# ProPrj_ZC95_FrontPanelControls_v1_1.net
KiCad netlist of a schematic drawn in EasyEDA Pro
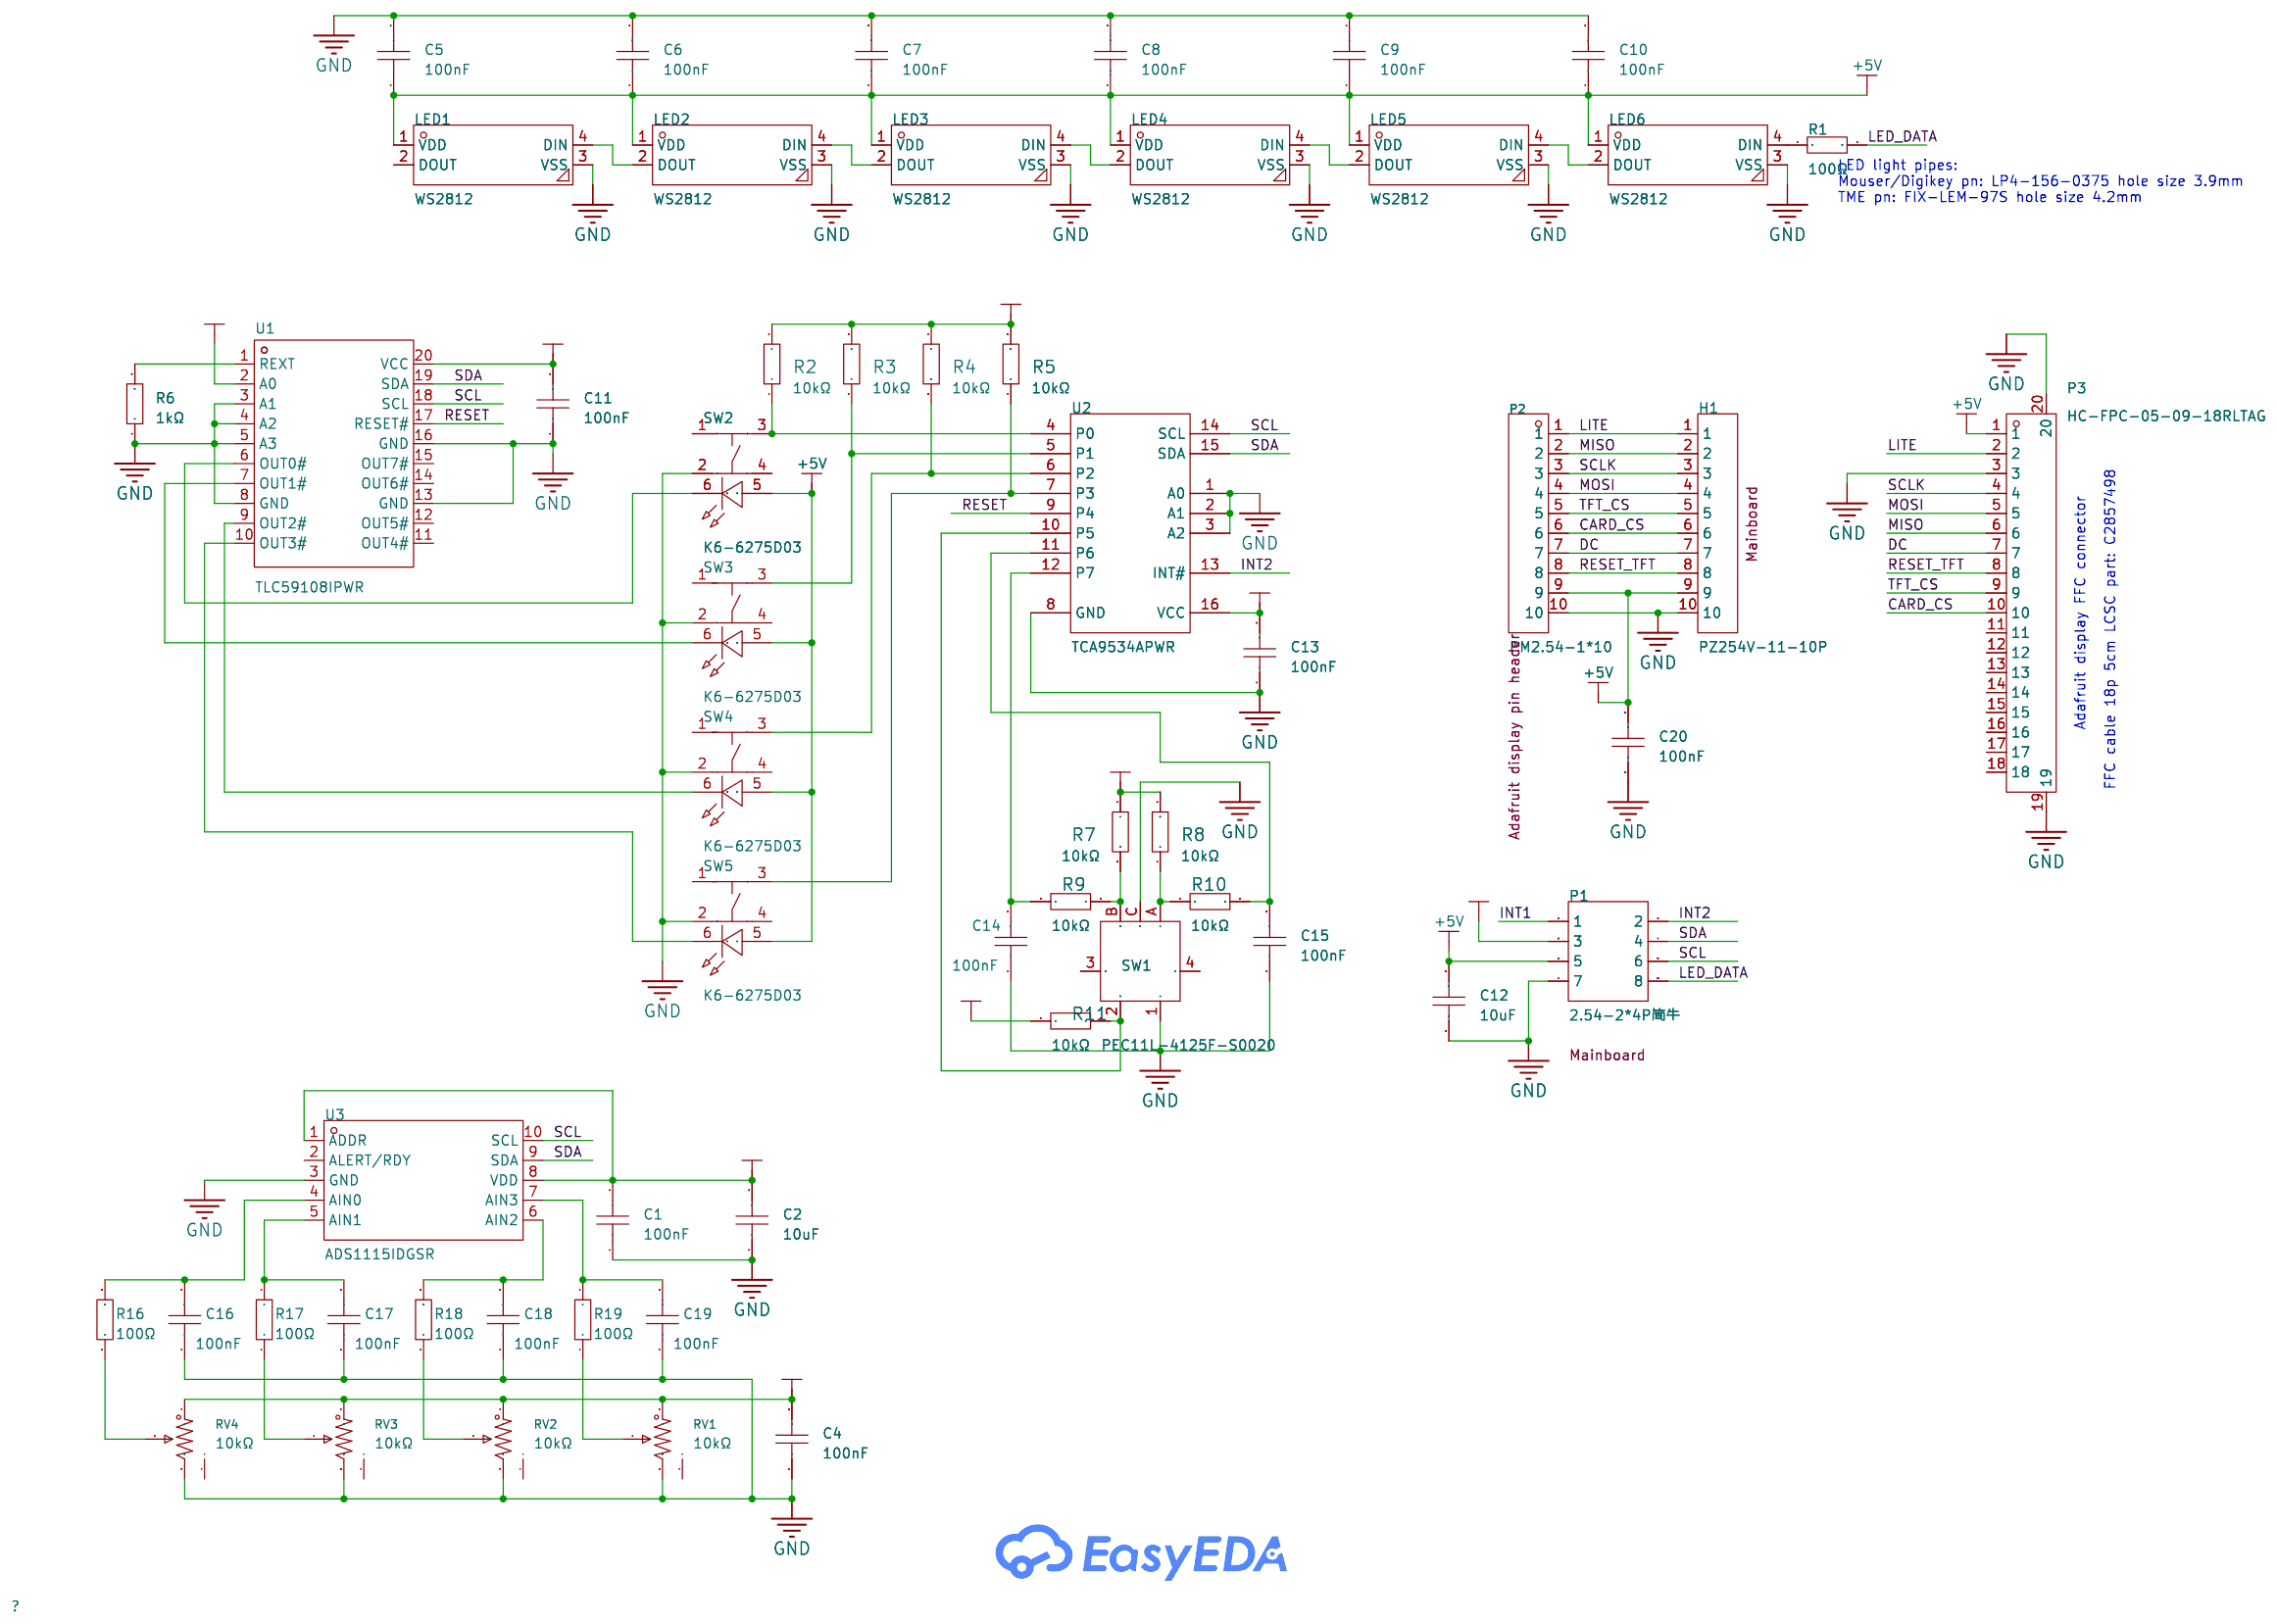
[diagram p0: schematic sheet]

(export (version "E")
  (design (tool "Eeschema 10.0.6"))
  (components
    (comp (ref "C1")
      (value "100nF")
      (footprint "easyedapro:C0603")
      (description "Capacitance:100nF Tolerance:±10% Tolerance:±10% Voltage Rating:50V Temperature Coefficient:X7R")
      (fields
        (field (name "Manufacturer Part") "CC0603KRX7R9BB104")
        (field (name "Manufacturer") "YAGEO(国巨)")
      )
      (libsource (lib "easyedapro") (part "CC0603KRX7R9BB104"))
    )
    (comp (ref "C2")
      (value "10uF")
      (footprint "easyedapro:C0603")
      (description "Capacitance:10uF Tolerance:±10% Tolerance:±10% Voltage Rating:10V Temperature Coefficient:X5R")
      (fields
        (field (name "Manufacturer Part") "CL10A106KP8NNNC")
        (field (name "Manufacturer") "SAMSUNG(三星)")
      )
      (libsource (lib "easyedapro") (part "CL10A106KP8NNNC"))
    )
    (comp (ref "C4")
      (value "100nF")
      (footprint "easyedapro:C0603")
      (description "Capacitance:100nF Tolerance:±10% Tolerance:±10% Voltage Rating:50V Temperature Coefficient:X7R")
      (fields
        (field (name "Manufacturer Part") "CC0603KRX7R9BB104")
        (field (name "Manufacturer") "YAGEO(国巨)")
      )
      (libsource (lib "easyedapro") (part "CC0603KRX7R9BB104"))
    )
    (comp (ref "C5")
      (value "100nF")
      (footprint "easyedapro:C0603")
      (description "Capacitance:100nF Tolerance:±10% Tolerance:±10% Voltage Rating:50V Temperature Coefficient:X7R")
      (fields
        (field (name "Manufacturer Part") "CC0603KRX7R9BB104")
        (field (name "Manufacturer") "YAGEO(国巨)")
      )
      (libsource (lib "easyedapro") (part "CC0603KRX7R9BB104"))
    )
    (comp (ref "C6")
      (value "100nF")
      (footprint "easyedapro:C0603")
      (description "Capacitance:100nF Tolerance:±10% Tolerance:±10% Voltage Rating:50V Temperature Coefficient:X7R")
      (fields
        (field (name "Manufacturer Part") "CC0603KRX7R9BB104")
        (field (name "Manufacturer") "YAGEO(国巨)")
      )
      (libsource (lib "easyedapro") (part "CC0603KRX7R9BB104"))
    )
    (comp (ref "C7")
      (value "100nF")
      (footprint "easyedapro:C0603")
      (description "Capacitance:100nF Tolerance:±10% Tolerance:±10% Voltage Rating:50V Temperature Coefficient:X7R")
      (fields
        (field (name "Manufacturer Part") "CC0603KRX7R9BB104")
        (field (name "Manufacturer") "YAGEO(国巨)")
      )
      (libsource (lib "easyedapro") (part "CC0603KRX7R9BB104"))
    )
    (comp (ref "C8")
      (value "100nF")
      (footprint "easyedapro:C0603")
      (description "Capacitance:100nF Tolerance:±10% Tolerance:±10% Voltage Rating:50V Temperature Coefficient:X7R")
      (fields
        (field (name "Manufacturer Part") "CC0603KRX7R9BB104")
        (field (name "Manufacturer") "YAGEO(国巨)")
      )
      (libsource (lib "easyedapro") (part "CC0603KRX7R9BB104"))
    )
    (comp (ref "C9")
      (value "100nF")
      (footprint "easyedapro:C0603")
      (description "Capacitance:100nF Tolerance:±10% Tolerance:±10% Voltage Rating:50V Temperature Coefficient:X7R")
      (fields
        (field (name "Manufacturer Part") "CC0603KRX7R9BB104")
        (field (name "Manufacturer") "YAGEO(国巨)")
      )
      (libsource (lib "easyedapro") (part "CC0603KRX7R9BB104"))
    )
    (comp (ref "C10")
      (value "100nF")
      (footprint "easyedapro:C0603")
      (description "Capacitance:100nF Tolerance:±10% Tolerance:±10% Voltage Rating:50V Temperature Coefficient:X7R")
      (fields
        (field (name "Manufacturer Part") "CC0603KRX7R9BB104")
        (field (name "Manufacturer") "YAGEO(国巨)")
      )
      (libsource (lib "easyedapro") (part "CC0603KRX7R9BB104"))
    )
    (comp (ref "C11")
      (value "100nF")
      (footprint "easyedapro:C0603")
      (description "Capacitance:100nF Tolerance:±10% Tolerance:±10% Voltage Rating:50V Temperature Coefficient:X7R")
      (fields
        (field (name "Manufacturer Part") "CC0603KRX7R9BB104")
        (field (name "Manufacturer") "YAGEO(国巨)")
      )
      (libsource (lib "easyedapro") (part "CC0603KRX7R9BB104"))
    )
    (comp (ref "C12")
      (value "10uF")
      (footprint "easyedapro:C0603")
      (description "Capacitance:10uF Tolerance:±10% Tolerance:±10% Voltage Rating:10V Temperature Coefficient:X5R")
      (fields
        (field (name "Manufacturer Part") "CL10A106KP8NNNC")
        (field (name "Manufacturer") "SAMSUNG(三星)")
      )
      (libsource (lib "easyedapro") (part "CL10A106KP8NNNC"))
    )
    (comp (ref "C13")
      (value "100nF")
      (footprint "easyedapro:C0603")
      (description "Capacitance:100nF Tolerance:±10% Tolerance:±10% Voltage Rating:50V Temperature Coefficient:X7R")
      (fields
        (field (name "Manufacturer Part") "CC0603KRX7R9BB104")
        (field (name "Manufacturer") "YAGEO(国巨)")
      )
      (libsource (lib "easyedapro") (part "CC0603KRX7R9BB104"))
    )
    (comp (ref "C14")
      (value "100nF")
      (footprint "easyedapro:C0603")
      (description "Capacitance:100nF Tolerance:±10% Tolerance:±10% Voltage Rating:50V Temperature Coefficient:X7R")
      (fields
        (field (name "Manufacturer Part") "CC0603KRX7R9BB104")
        (field (name "Manufacturer") "YAGEO(国巨)")
      )
      (libsource (lib "easyedapro") (part "CC0603KRX7R9BB104"))
    )
    (comp (ref "C15")
      (value "100nF")
      (footprint "easyedapro:C0603")
      (description "Capacitance:100nF Tolerance:±10% Tolerance:±10% Voltage Rating:50V Temperature Coefficient:X7R")
      (fields
        (field (name "Manufacturer Part") "CC0603KRX7R9BB104")
        (field (name "Manufacturer") "YAGEO(国巨)")
      )
      (libsource (lib "easyedapro") (part "CC0603KRX7R9BB104"))
    )
    (comp (ref "C16")
      (value "100nF")
      (footprint "easyedapro:C0603")
      (description "Capacitance:100nF Tolerance:±10% Tolerance:±10% Voltage Rating:50V Temperature Coefficient:X7R")
      (fields
        (field (name "Manufacturer Part") "CC0603KRX7R9BB104")
        (field (name "Manufacturer") "YAGEO(国巨)")
      )
      (libsource (lib "easyedapro") (part "CC0603KRX7R9BB104"))
    )
    (comp (ref "C17")
      (value "100nF")
      (footprint "easyedapro:C0603")
      (description "Capacitance:100nF Tolerance:±10% Tolerance:±10% Voltage Rating:50V Temperature Coefficient:X7R")
      (fields
        (field (name "Manufacturer Part") "CC0603KRX7R9BB104")
        (field (name "Manufacturer") "YAGEO(国巨)")
      )
      (libsource (lib "easyedapro") (part "CC0603KRX7R9BB104"))
    )
    (comp (ref "C18")
      (value "100nF")
      (footprint "easyedapro:C0603")
      (description "Capacitance:100nF Tolerance:±10% Tolerance:±10% Voltage Rating:50V Temperature Coefficient:X7R")
      (fields
        (field (name "Manufacturer Part") "CC0603KRX7R9BB104")
        (field (name "Manufacturer") "YAGEO(国巨)")
      )
      (libsource (lib "easyedapro") (part "CC0603KRX7R9BB104"))
    )
    (comp (ref "C19")
      (value "100nF")
      (footprint "easyedapro:C0603")
      (description "Capacitance:100nF Tolerance:±10% Tolerance:±10% Voltage Rating:50V Temperature Coefficient:X7R")
      (fields
        (field (name "Manufacturer Part") "CC0603KRX7R9BB104")
        (field (name "Manufacturer") "YAGEO(国巨)")
      )
      (libsource (lib "easyedapro") (part "CC0603KRX7R9BB104"))
    )
    (comp (ref "C20")
      (value "100nF")
      (footprint "easyedapro:C0603")
      (description "Capacitance:100nF Tolerance:±10% Tolerance:±10% Voltage Rating:50V Temperature Coefficient:X7R")
      (fields
        (field (name "Manufacturer Part") "CC0603KRX7R9BB104")
        (field (name "Manufacturer") "YAGEO(国巨)")
      )
      (libsource (lib "easyedapro") (part "CC0603KRX7R9BB104"))
    )
    (comp (ref "H1")
      (value "PZ254V-11-10P")
      (footprint "easyedapro:HDR-TH_10P-P2.54-V-M")
      (fields (field (name "Manufacturer") "XFCN(兴飞)") (field (name "Comment") "Mainboard"))
      (libsource (lib "easyedapro") (part "PZ254V-11-10P"))
    )
    (comp (ref "LED1")
      (value "WS2812")
      (footprint "easyedapro:LED-SMD_4P-L5.0-W5.0-TL_WS2812B-B")
      (fields (field (name "Manufacturer") "worldsemi"))
      (libsource (lib "easyedapro") (part "WS2812B-B/W"))
    )
    (comp (ref "LED2")
      (value "WS2812")
      (footprint "easyedapro:LED-SMD_4P-L5.0-W5.0-TL_WS2812B-B")
      (fields (field (name "Manufacturer") "worldsemi"))
      (libsource (lib "easyedapro") (part "WS2812B-B/W"))
    )
    (comp (ref "LED3")
      (value "WS2812")
      (footprint "easyedapro:LED-SMD_4P-L5.0-W5.0-TL_WS2812B-B")
      (fields (field (name "Manufacturer") "worldsemi"))
      (libsource (lib "easyedapro") (part "WS2812B-B/W"))
    )
    (comp (ref "LED4")
      (value "WS2812")
      (footprint "easyedapro:LED-SMD_4P-L5.0-W5.0-TL_WS2812B-B")
      (fields (field (name "Manufacturer") "worldsemi"))
      (libsource (lib "easyedapro") (part "WS2812B-B/W"))
    )
    (comp (ref "LED5")
      (value "WS2812")
      (footprint "easyedapro:LED-SMD_4P-L5.0-W5.0-TL_WS2812B-B")
      (fields (field (name "Manufacturer") "worldsemi"))
      (libsource (lib "easyedapro") (part "WS2812B-B/W"))
    )
    (comp (ref "LED6")
      (value "WS2812")
      (footprint "easyedapro:LED-SMD_4P-L5.0-W5.0-TL_WS2812B-B")
      (fields (field (name "Manufacturer") "worldsemi"))
      (libsource (lib "easyedapro") (part "WS2812B-B/W"))
    )
    (comp (ref "P1")
      (value "2.54-2*4P简牛")
      (footprint "easyedapro:IDC-TH_8P-P2.54-V-R2-C4-S2.54")
      (fields (field (name "Manufacturer") "BOOMELE(博穆精密)") (field (name "Comment") "Mainboard"))
      (libsource (lib "easyedapro") (part "HDR-IDC-2.54-2X4P"))
    )
    (comp (ref "P2")
      (value "PM2.54-1*10")
      (footprint "easyedapro:HDR-TH_10P-P2.54-V-F")
      (fields
        (field (name "Manufacturer") "ZHOURI(洲日)")
        (field (name "Comment") "Adafruit display pin header")
      )
      (libsource (lib "easyedapro") (part "PM2.54-1*10"))
    )
    (comp (ref "P3")
      (value "HC-FPC-05-09-18RLTAG")
      (footprint "easyedapro:FPC-SMD_18P-P0.50_HC-FPC-05-09-18RLTAG")
      (fields (field (name "Manufacturer") "HCTL(华灿天禄)"))
      (libsource (lib "easyedapro") (part "HC-FPC-05-09-18RLTAG"))
    )
    (comp (ref "R1")
      (value "100Ω")
      (footprint "easyedapro:R0603")
      (fields
        (field (name "Manufacturer Part") "0603WAF1000T5E")
        (field (name "Manufacturer") "UNI-ROYAL(厚声)")
      )
      (libsource (lib "easyedapro") (part "0603WAF1000T5E"))
    )
    (comp (ref "R2")
      (value "10kΩ")
      (footprint "easyedapro:R0603")
      (fields
        (field (name "Manufacturer Part") "0603WAF1002T5E")
        (field (name "Manufacturer") "UNI-ROYAL(厚声)")
      )
      (libsource (lib "easyedapro") (part "0603WAF1002T5E"))
    )
    (comp (ref "R3")
      (value "10kΩ")
      (footprint "easyedapro:R0603")
      (fields
        (field (name "Manufacturer Part") "0603WAF1002T5E")
        (field (name "Manufacturer") "UNI-ROYAL(厚声)")
      )
      (libsource (lib "easyedapro") (part "0603WAF1002T5E"))
    )
    (comp (ref "R4")
      (value "10kΩ")
      (footprint "easyedapro:R0603")
      (fields
        (field (name "Manufacturer Part") "0603WAF1002T5E")
        (field (name "Manufacturer") "UNI-ROYAL(厚声)")
      )
      (libsource (lib "easyedapro") (part "0603WAF1002T5E"))
    )
    (comp (ref "R5")
      (value "10kΩ")
      (footprint "easyedapro:R0603")
      (fields
        (field (name "Manufacturer Part") "0603WAF1002T5E")
        (field (name "Manufacturer") "UNI-ROYAL(厚声)")
      )
      (libsource (lib "easyedapro") (part "0603WAF1002T5E"))
    )
    (comp (ref "R6")
      (value "1kΩ")
      (footprint "easyedapro:R0603")
      (fields
        (field (name "Manufacturer Part") "0603WAF1001T5E")
        (field (name "Manufacturer") "UNI-ROYAL(厚声)")
      )
      (libsource (lib "easyedapro") (part "0603WAF1001T5E"))
    )
    (comp (ref "R7")
      (value "10kΩ")
      (footprint "easyedapro:R0603")
      (fields
        (field (name "Manufacturer Part") "0603WAF1002T5E")
        (field (name "Manufacturer") "UNI-ROYAL(厚声)")
      )
      (libsource (lib "easyedapro") (part "0603WAF1002T5E"))
    )
    (comp (ref "R8")
      (value "10kΩ")
      (footprint "easyedapro:R0603")
      (fields
        (field (name "Manufacturer Part") "0603WAF1002T5E")
        (field (name "Manufacturer") "UNI-ROYAL(厚声)")
      )
      (libsource (lib "easyedapro") (part "0603WAF1002T5E"))
    )
    (comp (ref "R9")
      (value "10kΩ")
      (footprint "easyedapro:R0603")
      (fields
        (field (name "Manufacturer Part") "0603WAF1002T5E")
        (field (name "Manufacturer") "UNI-ROYAL(厚声)")
      )
      (libsource (lib "easyedapro") (part "0603WAF1002T5E"))
    )
    (comp (ref "R10")
      (value "10kΩ")
      (footprint "easyedapro:R0603")
      (fields
        (field (name "Manufacturer Part") "0603WAF1002T5E")
        (field (name "Manufacturer") "UNI-ROYAL(厚声)")
      )
      (libsource (lib "easyedapro") (part "0603WAF1002T5E"))
    )
    (comp (ref "R11")
      (value "10kΩ")
      (footprint "easyedapro:R0603")
      (fields
        (field (name "Manufacturer Part") "0603WAF1002T5E")
        (field (name "Manufacturer") "UNI-ROYAL(厚声)")
      )
      (libsource (lib "easyedapro") (part "0603WAF1002T5E"))
    )
    (comp (ref "R16")
      (value "100Ω")
      (footprint "easyedapro:R0603")
      (fields
        (field (name "Manufacturer Part") "0603WAF1000T5E")
        (field (name "Manufacturer") "UNI-ROYAL(厚声)")
      )
      (libsource (lib "easyedapro") (part "0603WAF1000T5E"))
    )
    (comp (ref "R17")
      (value "100Ω")
      (footprint "easyedapro:R0603")
      (fields
        (field (name "Manufacturer Part") "0603WAF1000T5E")
        (field (name "Manufacturer") "UNI-ROYAL(厚声)")
      )
      (libsource (lib "easyedapro") (part "0603WAF1000T5E"))
    )
    (comp (ref "R18")
      (value "100Ω")
      (footprint "easyedapro:R0603")
      (fields
        (field (name "Manufacturer Part") "0603WAF1000T5E")
        (field (name "Manufacturer") "UNI-ROYAL(厚声)")
      )
      (libsource (lib "easyedapro") (part "0603WAF1000T5E"))
    )
    (comp (ref "R19")
      (value "100Ω")
      (footprint "easyedapro:R0603")
      (fields
        (field (name "Manufacturer Part") "0603WAF1000T5E")
        (field (name "Manufacturer") "UNI-ROYAL(厚声)")
      )
      (libsource (lib "easyedapro") (part "0603WAF1000T5E"))
    )
    (comp (ref "RV1")
      (value "10kΩ")
      (footprint "easyedapro:RES-ADJ-TH_RK09L1140A65")
      (fields
        (field (name "Manufacturer Part") "RK09L1140A2U")
        (field (name "Manufacturer") "ALPSALPINE(阿尔卑斯阿尔派)")
      )
      (libsource (lib "easyedapro") (part "RK09L1140A2U"))
    )
    (comp (ref "RV2")
      (value "10kΩ")
      (footprint "easyedapro:RES-ADJ-TH_RK09L1140A65")
      (fields
        (field (name "Manufacturer Part") "RK09L1140A2U")
        (field (name "Manufacturer") "ALPSALPINE(阿尔卑斯阿尔派)")
      )
      (libsource (lib "easyedapro") (part "RK09L1140A2U"))
    )
    (comp (ref "RV3")
      (value "10kΩ")
      (footprint "easyedapro:RES-ADJ-TH_RK09L1140A65")
      (fields
        (field (name "Manufacturer Part") "RK09L1140A2U")
        (field (name "Manufacturer") "ALPSALPINE(阿尔卑斯阿尔派)")
      )
      (libsource (lib "easyedapro") (part "RK09L1140A2U"))
    )
    (comp (ref "RV4")
      (value "10kΩ")
      (footprint "easyedapro:RES-ADJ-TH_RK09L1140A65")
      (fields
        (field (name "Manufacturer Part") "RK09L1140A2U")
        (field (name "Manufacturer") "ALPSALPINE(阿尔卑斯阿尔派)")
      )
      (libsource (lib "easyedapro") (part "RK09L1140A2U"))
    )
    (comp (ref "SW1")
      (value "PEC11L-4125F-S0020")
      (footprint "easyedapro:SW-TH_PEC11L-4125F-S0020")
      (fields (field (name "Manufacturer") "BOURNS"))
      (libsource (lib "easyedapro") (part "PEC11L-4125F-S0020"))
    )
    (comp (ref "SW2")
      (value "K6-6275D03")
      (footprint "easyedapro:SW-TH_K6-6275D03")
      (fields (field (name "Manufacturer") "韩国韩荣"))
      (libsource (lib "easyedapro") (part "K6-6275D03"))
    )
    (comp (ref "SW3")
      (value "K6-6275D03")
      (footprint "easyedapro:SW-TH_K6-6275D03")
      (fields (field (name "Manufacturer") "韩国韩荣"))
      (libsource (lib "easyedapro") (part "K6-6275D03"))
    )
    (comp (ref "SW4")
      (value "K6-6275D03")
      (footprint "easyedapro:SW-TH_K6-6275D03")
      (fields (field (name "Manufacturer") "韩国韩荣"))
      (libsource (lib "easyedapro") (part "K6-6275D03"))
    )
    (comp (ref "SW5")
      (value "K6-6275D03")
      (footprint "easyedapro:SW-TH_K6-6275D03")
      (fields (field (name "Manufacturer") "韩国韩荣"))
      (libsource (lib "easyedapro") (part "K6-6275D03"))
    )
    (comp (ref "U1")
      (value "TLC59108IPWR")
      (footprint "easyedapro:TSSOP-20_L6.5-W4.4-P0.65-LS6.4-BL")
      (fields (field (name "Manufacturer") "TI(德州仪器)"))
      (libsource (lib "easyedapro") (part "TLC59108IPWR"))
    )
    (comp (ref "U2")
      (value "TCA9534APWR")
      (footprint "easyedapro:TSSOP-16_L5.0-W4.4-P0.65-LS6.4-BL")
      (fields (field (name "Manufacturer") "TI(德州仪器)"))
      (libsource (lib "easyedapro") (part "TCA9534APWR"))
    )
    (comp (ref "U3")
      (value "ADS1115IDGSR")
      (footprint "easyedapro:MSOP-10_L3.0-W3.0-P0.50-LS5.0-BL")
      (fields (field (name "Manufacturer") "TI(德州仪器)"))
      (libsource (lib "easyedapro") (part "ADS1115IDGSR"))
    )
  )
  (nets
    (net (code "1") (name "+3V3") (class "Default")
      (node (ref "C1") (pin "2") (pinfunction "2_2") (pintype "unspecified"))
      (node (ref "C11") (pin "2") (pinfunction "2_2") (pintype "unspecified"))
      (node (ref "C13") (pin "2") (pinfunction "2_2") (pintype "unspecified"))
      (node (ref "C2") (pin "2") (pinfunction "2_2") (pintype "unspecified"))
      (node (ref "C4") (pin "2") (pinfunction "2_2") (pintype "unspecified"))
      (node (ref "P1") (pin "3") (pinfunction "3_3") (pintype "input"))
      (node (ref "R11") (pin "1") (pinfunction "1_1") (pintype "input"))
      (node (ref "R2") (pin "2") (pinfunction "2_2") (pintype "input"))
      (node (ref "R3") (pin "2") (pinfunction "2_2") (pintype "input"))
      (node (ref "R4") (pin "1") (pinfunction "1_1") (pintype "input"))
      (node (ref "R5") (pin "2") (pinfunction "2_2") (pintype "input"))
      (node (ref "R7") (pin "1") (pinfunction "1_1") (pintype "input"))
      (node (ref "R8") (pin "2") (pinfunction "2_2") (pintype "input"))
      (node (ref "RV1") (pin "1") (pinfunction "1_1") (pintype "input"))
      (node (ref "RV2") (pin "1") (pinfunction "1_1") (pintype "input"))
      (node (ref "RV3") (pin "1") (pinfunction "1_1") (pintype "input"))
      (node (ref "RV4") (pin "1") (pinfunction "1_1") (pintype "input"))
      (node (ref "U1") (pin "2") (pinfunction "A0_2") (pintype "unspecified"))
      (node (ref "U1") (pin "20") (pinfunction "VCC_20") (pintype "unspecified"))
      (node (ref "U2") (pin "16") (pinfunction "VCC_16") (pintype "unspecified"))
      (node (ref "U3") (pin "1") (pinfunction "ADDR_1") (pintype "unspecified"))
      (node (ref "U3") (pin "8") (pinfunction "VDD_8") (pintype "unspecified"))
    )
    (net (code "2") (name "+5V") (class "Default")
      (node (ref "C10") (pin "1") (pinfunction "1_1") (pintype "unspecified"))
      (node (ref "C12") (pin "2") (pinfunction "2_2") (pintype "unspecified"))
      (node (ref "C20") (pin "2") (pinfunction "2_2") (pintype "unspecified"))
      (node (ref "C5") (pin "1") (pinfunction "1_1") (pintype "unspecified"))
      (node (ref "C6") (pin "1") (pinfunction "1_1") (pintype "unspecified"))
      (node (ref "C7") (pin "1") (pinfunction "1_1") (pintype "unspecified"))
      (node (ref "C8") (pin "1") (pinfunction "1_1") (pintype "unspecified"))
      (node (ref "C9") (pin "1") (pinfunction "1_1") (pintype "unspecified"))
      (node (ref "H1") (pin "9") (pinfunction "9_9") (pintype "unspecified"))
      (node (ref "LED1") (pin "1") (pinfunction "VDD_1") (pintype "unspecified"))
      (node (ref "LED2") (pin "1") (pinfunction "VDD_1") (pintype "unspecified"))
      (node (ref "LED3") (pin "1") (pinfunction "VDD_1") (pintype "unspecified"))
      (node (ref "LED4") (pin "1") (pinfunction "VDD_1") (pintype "unspecified"))
      (node (ref "LED5") (pin "1") (pinfunction "VDD_1") (pintype "unspecified"))
      (node (ref "LED6") (pin "1") (pinfunction "VDD_1") (pintype "unspecified"))
      (node (ref "P1") (pin "5") (pinfunction "5_5") (pintype "input"))
      (node (ref "P2") (pin "9") (pinfunction "9_9") (pintype "input"))
      (node (ref "P3") (pin "1") (pinfunction "1_1") (pintype "unspecified"))
      (node (ref "SW2") (pin "5") (pinfunction "5_5") (pintype "unspecified"))
      (node (ref "SW3") (pin "5") (pinfunction "5_5") (pintype "unspecified"))
      (node (ref "SW4") (pin "5") (pinfunction "5_5") (pintype "unspecified"))
      (node (ref "SW5") (pin "5") (pinfunction "5_5") (pintype "unspecified"))
    )
    (net (code "3") (name "/CARD_CS") (class "Default")
      (node (ref "H1") (pin "6") (pinfunction "6_6") (pintype "unspecified"))
      (node (ref "P2") (pin "6") (pinfunction "6_6") (pintype "input"))
      (node (ref "P3") (pin "10") (pinfunction "10_10") (pintype "unspecified"))
    )
    (net (code "4") (name "/DC") (class "Default")
      (node (ref "H1") (pin "7") (pinfunction "7_7") (pintype "unspecified"))
      (node (ref "P2") (pin "7") (pinfunction "7_7") (pintype "input"))
      (node (ref "P3") (pin "7") (pinfunction "7_7") (pintype "unspecified"))
    )
    (net (code "5") (name "/INT1") (class "Default")
      (node (ref "P1") (pin "1") (pinfunction "1_1") (pintype "input"))
    )
    (net (code "6") (name "/INT2") (class "Default")
      (node (ref "P1") (pin "2") (pinfunction "2_2") (pintype "input"))
      (node (ref "U2") (pin "13") (pinfunction "INT#_13") (pintype "unspecified"))
    )
    (net (code "7") (name "/LED_DATA") (class "Default")
      (node (ref "P1") (pin "8") (pinfunction "8_8") (pintype "input"))
      (node (ref "R1") (pin "2") (pinfunction "2_2") (pintype "input"))
    )
    (net (code "8") (name "/LITE") (class "Default")
      (node (ref "H1") (pin "1") (pinfunction "1_1") (pintype "unspecified"))
      (node (ref "P2") (pin "1") (pinfunction "1_1") (pintype "input"))
      (node (ref "P3") (pin "2") (pinfunction "2_2") (pintype "unspecified"))
    )
    (net (code "9") (name "/MISO") (class "Default")
      (node (ref "H1") (pin "2") (pinfunction "2_2") (pintype "unspecified"))
      (node (ref "P2") (pin "2") (pinfunction "2_2") (pintype "input"))
      (node (ref "P3") (pin "6") (pinfunction "6_6") (pintype "unspecified"))
    )
    (net (code "10") (name "/MOSI") (class "Default")
      (node (ref "H1") (pin "4") (pinfunction "4_4") (pintype "unspecified"))
      (node (ref "P2") (pin "4") (pinfunction "4_4") (pintype "input"))
      (node (ref "P3") (pin "5") (pinfunction "5_5") (pintype "unspecified"))
    )
    (net (code "11") (name "/RESET") (class "Default")
      (node (ref "U1") (pin "17") (pinfunction "RESET#_17") (pintype "unspecified"))
      (node (ref "U2") (pin "9") (pinfunction "P4_9") (pintype "bidirectional"))
    )
    (net (code "12") (name "/RESET_TFT") (class "Default")
      (node (ref "H1") (pin "8") (pinfunction "8_8") (pintype "unspecified"))
      (node (ref "P2") (pin "8") (pinfunction "8_8") (pintype "input"))
      (node (ref "P3") (pin "8") (pinfunction "8_8") (pintype "unspecified"))
    )
    (net (code "13") (name "/SCL") (class "Default")
      (node (ref "P1") (pin "6") (pinfunction "6_6") (pintype "input"))
      (node (ref "U1") (pin "18") (pinfunction "SCL_18") (pintype "unspecified"))
      (node (ref "U2") (pin "14") (pinfunction "SCL_14") (pintype "unspecified"))
      (node (ref "U3") (pin "10") (pinfunction "SCL_10") (pintype "unspecified"))
    )
    (net (code "14") (name "/SCLK") (class "Default")
      (node (ref "H1") (pin "3") (pinfunction "3_3") (pintype "unspecified"))
      (node (ref "P2") (pin "3") (pinfunction "3_3") (pintype "input"))
      (node (ref "P3") (pin "4") (pinfunction "4_4") (pintype "unspecified"))
    )
    (net (code "15") (name "/SDA") (class "Default")
      (node (ref "P1") (pin "4") (pinfunction "4_4") (pintype "input"))
      (node (ref "U1") (pin "19") (pinfunction "SDA_19") (pintype "unspecified"))
      (node (ref "U2") (pin "15") (pinfunction "SDA_15") (pintype "bidirectional"))
      (node (ref "U3") (pin "9") (pinfunction "SDA_9") (pintype "unspecified"))
    )
    (net (code "16") (name "/TFT_CS") (class "Default")
      (node (ref "H1") (pin "5") (pinfunction "5_5") (pintype "unspecified"))
      (node (ref "P2") (pin "5") (pinfunction "5_5") (pintype "input"))
      (node (ref "P3") (pin "9") (pinfunction "9_9") (pintype "unspecified"))
    )
    (net (code "17") (name "GND") (class "Default")
      (node (ref "C1") (pin "1") (pinfunction "1_1") (pintype "unspecified"))
      (node (ref "C10") (pin "2") (pinfunction "2_2") (pintype "unspecified"))
      (node (ref "C11") (pin "1") (pinfunction "1_1") (pintype "unspecified"))
      (node (ref "C12") (pin "1") (pinfunction "1_1") (pintype "unspecified"))
      (node (ref "C13") (pin "1") (pinfunction "1_1") (pintype "unspecified"))
      (node (ref "C14") (pin "1") (pinfunction "1_1") (pintype "unspecified"))
      (node (ref "C15") (pin "1") (pinfunction "1_1") (pintype "unspecified"))
      (node (ref "C16") (pin "1") (pinfunction "1_1") (pintype "unspecified"))
      (node (ref "C17") (pin "1") (pinfunction "1_1") (pintype "unspecified"))
      (node (ref "C18") (pin "1") (pinfunction "1_1") (pintype "unspecified"))
      (node (ref "C19") (pin "1") (pinfunction "1_1") (pintype "unspecified"))
      (node (ref "C2") (pin "1") (pinfunction "1_1") (pintype "unspecified"))
      (node (ref "C20") (pin "1") (pinfunction "1_1") (pintype "unspecified"))
      (node (ref "C4") (pin "1") (pinfunction "1_1") (pintype "unspecified"))
      (node (ref "C5") (pin "2") (pinfunction "2_2") (pintype "unspecified"))
      (node (ref "C6") (pin "2") (pinfunction "2_2") (pintype "unspecified"))
      (node (ref "C7") (pin "2") (pinfunction "2_2") (pintype "unspecified"))
      (node (ref "C8") (pin "2") (pinfunction "2_2") (pintype "unspecified"))
      (node (ref "C9") (pin "2") (pinfunction "2_2") (pintype "unspecified"))
      (node (ref "H1") (pin "10") (pinfunction "10_10") (pintype "unspecified"))
      (node (ref "LED1") (pin "3") (pinfunction "VSS_3") (pintype "unspecified"))
      (node (ref "LED2") (pin "3") (pinfunction "VSS_3") (pintype "unspecified"))
      (node (ref "LED3") (pin "3") (pinfunction "VSS_3") (pintype "unspecified"))
      (node (ref "LED4") (pin "3") (pinfunction "VSS_3") (pintype "unspecified"))
      (node (ref "LED5") (pin "3") (pinfunction "VSS_3") (pintype "unspecified"))
      (node (ref "LED6") (pin "3") (pinfunction "VSS_3") (pintype "unspecified"))
      (node (ref "P1") (pin "7") (pinfunction "7_7") (pintype "input"))
      (node (ref "P2") (pin "10") (pinfunction "10_10") (pintype "input"))
      (node (ref "P3") (pin "19") (pinfunction "19_19") (pintype "unspecified"))
      (node (ref "P3") (pin "20") (pinfunction "20_20") (pintype "unspecified"))
      (node (ref "P3") (pin "3") (pinfunction "3_3") (pintype "unspecified"))
      (node (ref "R6") (pin "1") (pinfunction "1_1") (pintype "input"))
      (node (ref "RV1") (pin "3") (pinfunction "3_3") (pintype "input"))
      (node (ref "RV2") (pin "3") (pinfunction "3_3") (pintype "input"))
      (node (ref "RV3") (pin "3") (pinfunction "3_3") (pintype "input"))
      (node (ref "RV4") (pin "3") (pinfunction "3_3") (pintype "input"))
      (node (ref "SW1") (pin "1") (pinfunction "1_1") (pintype "unspecified"))
      (node (ref "SW1") (pin "C") (pinfunction "C_C") (pintype "unspecified"))
      (node (ref "SW2") (pin "2") (pinfunction "2_2") (pintype "unspecified"))
      (node (ref "SW3") (pin "2") (pinfunction "2_2") (pintype "unspecified"))
      (node (ref "SW4") (pin "2") (pinfunction "2_2") (pintype "unspecified"))
      (node (ref "SW5") (pin "2") (pinfunction "2_2") (pintype "unspecified"))
      (node (ref "U1") (pin "13") (pinfunction "GND_13") (pintype "unspecified"))
      (node (ref "U1") (pin "16") (pinfunction "GND_16") (pintype "unspecified"))
      (node (ref "U1") (pin "3") (pinfunction "A1_3") (pintype "unspecified"))
      (node (ref "U1") (pin "4") (pinfunction "A2_4") (pintype "unspecified"))
      (node (ref "U1") (pin "5") (pinfunction "A3_5") (pintype "unspecified"))
      (node (ref "U1") (pin "8") (pinfunction "GND_8") (pintype "unspecified"))
      (node (ref "U2") (pin "1") (pinfunction "A0_1") (pintype "unspecified"))
      (node (ref "U2") (pin "2") (pinfunction "A1_2") (pintype "unspecified"))
      (node (ref "U2") (pin "3") (pinfunction "A2_3") (pintype "unspecified"))
      (node (ref "U2") (pin "8") (pinfunction "GND_8") (pintype "unspecified"))
      (node (ref "U3") (pin "3") (pinfunction "GND_3") (pintype "unspecified"))
    )
    (net (code "18") (name "Net-(LED1-DIN)") (class "Default")
      (node (ref "LED1") (pin "4") (pinfunction "DIN_4") (pintype "unspecified"))
      (node (ref "LED2") (pin "2") (pinfunction "DOUT_2") (pintype "unspecified"))
    )
    (net (code "19") (name "Net-(LED2-DIN)") (class "Default")
      (node (ref "LED2") (pin "4") (pinfunction "DIN_4") (pintype "unspecified"))
      (node (ref "LED3") (pin "2") (pinfunction "DOUT_2") (pintype "unspecified"))
    )
    (net (code "20") (name "Net-(LED3-DIN)") (class "Default")
      (node (ref "LED3") (pin "4") (pinfunction "DIN_4") (pintype "unspecified"))
      (node (ref "LED4") (pin "2") (pinfunction "DOUT_2") (pintype "unspecified"))
    )
    (net (code "21") (name "Net-(LED4-DIN)") (class "Default")
      (node (ref "LED4") (pin "4") (pinfunction "DIN_4") (pintype "unspecified"))
      (node (ref "LED5") (pin "2") (pinfunction "DOUT_2") (pintype "unspecified"))
    )
    (net (code "22") (name "Net-(LED5-DIN)") (class "Default")
      (node (ref "LED5") (pin "4") (pinfunction "DIN_4") (pintype "unspecified"))
      (node (ref "LED6") (pin "2") (pinfunction "DOUT_2") (pintype "unspecified"))
    )
    (net (code "23") (name "Net-(LED6-DIN)") (class "Default")
      (node (ref "LED6") (pin "4") (pinfunction "DIN_4") (pintype "unspecified"))
      (node (ref "R1") (pin "1") (pinfunction "1_1") (pintype "input"))
    )
    (net (code "24") (name "Net-(R7-Pad2)") (class "Default")
      (node (ref "R7") (pin "2") (pinfunction "2_2") (pintype "input"))
      (node (ref "R9") (pin "2") (pinfunction "2_2") (pintype "input"))
      (node (ref "SW1") (pin "B") (pinfunction "B_B") (pintype "unspecified"))
    )
    (net (code "25") (name "Net-(R10-Pad1)") (class "Default")
      (node (ref "R10") (pin "1") (pinfunction "1_1") (pintype "input"))
      (node (ref "R8") (pin "1") (pinfunction "1_1") (pintype "input"))
      (node (ref "SW1") (pin "A") (pinfunction "A_A") (pintype "unspecified"))
    )
    (net (code "26") (name "Net-(R16-Pad1)") (class "Default")
      (node (ref "R16") (pin "1") (pinfunction "1_1") (pintype "input"))
      (node (ref "RV4") (pin "2") (pinfunction "2_2") (pintype "input"))
    )
    (net (code "27") (name "Net-(R17-Pad1)") (class "Default")
      (node (ref "R17") (pin "1") (pinfunction "1_1") (pintype "input"))
      (node (ref "RV3") (pin "2") (pinfunction "2_2") (pintype "input"))
    )
    (net (code "28") (name "Net-(R18-Pad1)") (class "Default")
      (node (ref "R18") (pin "1") (pinfunction "1_1") (pintype "input"))
      (node (ref "RV2") (pin "2") (pinfunction "2_2") (pintype "input"))
    )
    (net (code "29") (name "Net-(R19-Pad1)") (class "Default")
      (node (ref "R19") (pin "1") (pinfunction "1_1") (pintype "input"))
      (node (ref "RV1") (pin "2") (pinfunction "2_2") (pintype "input"))
    )
    (net (code "30") (name "Net-(U1-OUT0#)") (class "Default")
      (node (ref "SW2") (pin "6") (pinfunction "6_6") (pintype "unspecified"))
      (node (ref "U1") (pin "6") (pinfunction "OUT0#_6") (pintype "unspecified"))
    )
    (net (code "31") (name "Net-(U1-OUT1#)") (class "Default")
      (node (ref "SW3") (pin "6") (pinfunction "6_6") (pintype "unspecified"))
      (node (ref "U1") (pin "7") (pinfunction "OUT1#_7") (pintype "unspecified"))
    )
    (net (code "32") (name "Net-(U1-OUT2#)") (class "Default")
      (node (ref "SW4") (pin "6") (pinfunction "6_6") (pintype "unspecified"))
      (node (ref "U1") (pin "9") (pinfunction "OUT2#_9") (pintype "unspecified"))
    )
    (net (code "33") (name "Net-(U1-OUT3#)") (class "Default")
      (node (ref "SW5") (pin "6") (pinfunction "6_6") (pintype "unspecified"))
      (node (ref "U1") (pin "10") (pinfunction "OUT3#_10") (pintype "unspecified"))
    )
    (net (code "34") (name "Net-(U1-REXT)") (class "Default")
      (node (ref "R6") (pin "2") (pinfunction "2_2") (pintype "input"))
      (node (ref "U1") (pin "1") (pinfunction "REXT_1") (pintype "unspecified"))
    )
    (net (code "35") (name "Net-(U2-P0)") (class "Default")
      (node (ref "R2") (pin "1") (pinfunction "1_1") (pintype "input"))
      (node (ref "SW2") (pin "3") (pinfunction "3_3") (pintype "unspecified"))
      (node (ref "U2") (pin "4") (pinfunction "P0_4") (pintype "bidirectional"))
    )
    (net (code "36") (name "Net-(U2-P1)") (class "Default")
      (node (ref "R3") (pin "1") (pinfunction "1_1") (pintype "input"))
      (node (ref "SW3") (pin "3") (pinfunction "3_3") (pintype "unspecified"))
      (node (ref "U2") (pin "5") (pinfunction "P1_5") (pintype "bidirectional"))
    )
    (net (code "37") (name "Net-(U2-P2)") (class "Default")
      (node (ref "R4") (pin "2") (pinfunction "2_2") (pintype "input"))
      (node (ref "SW4") (pin "3") (pinfunction "3_3") (pintype "unspecified"))
      (node (ref "U2") (pin "6") (pinfunction "P2_6") (pintype "bidirectional"))
    )
    (net (code "38") (name "Net-(U2-P3)") (class "Default")
      (node (ref "R5") (pin "1") (pinfunction "1_1") (pintype "input"))
      (node (ref "SW5") (pin "3") (pinfunction "3_3") (pintype "unspecified"))
      (node (ref "U2") (pin "7") (pinfunction "P3_7") (pintype "bidirectional"))
    )
    (net (code "39") (name "Net-(U2-P5)") (class "Default")
      (node (ref "R11") (pin "2") (pinfunction "2_2") (pintype "input"))
      (node (ref "SW1") (pin "2") (pinfunction "2_2") (pintype "unspecified"))
      (node (ref "U2") (pin "10") (pinfunction "P5_10") (pintype "bidirectional"))
    )
    (net (code "40") (name "Net-(U2-P6)") (class "Default")
      (node (ref "C15") (pin "2") (pinfunction "2_2") (pintype "unspecified"))
      (node (ref "R10") (pin "2") (pinfunction "2_2") (pintype "input"))
      (node (ref "U2") (pin "11") (pinfunction "P6_11") (pintype "bidirectional"))
    )
    (net (code "41") (name "Net-(U2-P7)") (class "Default")
      (node (ref "C14") (pin "2") (pinfunction "2_2") (pintype "unspecified"))
      (node (ref "R9") (pin "1") (pinfunction "1_1") (pintype "input"))
      (node (ref "U2") (pin "12") (pinfunction "P7_12") (pintype "bidirectional"))
    )
    (net (code "42") (name "Net-(U3-AIN0)") (class "Default")
      (node (ref "C16") (pin "2") (pinfunction "2_2") (pintype "unspecified"))
      (node (ref "R16") (pin "2") (pinfunction "2_2") (pintype "input"))
      (node (ref "U3") (pin "4") (pinfunction "AIN0_4") (pintype "unspecified"))
    )
    (net (code "43") (name "Net-(U3-AIN1)") (class "Default")
      (node (ref "C17") (pin "2") (pinfunction "2_2") (pintype "unspecified"))
      (node (ref "R17") (pin "2") (pinfunction "2_2") (pintype "input"))
      (node (ref "U3") (pin "5") (pinfunction "AIN1_5") (pintype "unspecified"))
    )
    (net (code "44") (name "Net-(U3-AIN2)") (class "Default")
      (node (ref "C18") (pin "2") (pinfunction "2_2") (pintype "unspecified"))
      (node (ref "R18") (pin "2") (pinfunction "2_2") (pintype "input"))
      (node (ref "U3") (pin "6") (pinfunction "AIN2_6") (pintype "unspecified"))
    )
    (net (code "45") (name "Net-(U3-AIN3)") (class "Default")
      (node (ref "C19") (pin "2") (pinfunction "2_2") (pintype "unspecified"))
      (node (ref "R19") (pin "2") (pinfunction "2_2") (pintype "input"))
      (node (ref "U3") (pin "7") (pinfunction "AIN3_7") (pintype "unspecified"))
    )
    (net (code "46") (name "unconnected-(LED1-DOUT-Pad2)") (class "Default")
      (node (ref "LED1") (pin "2") (pinfunction "DOUT_2") (pintype "unspecified"))
    )
    (net (code "47") (name "unconnected-(P3-Pad11)") (class "Default")
      (node (ref "P3") (pin "11") (pinfunction "11_11") (pintype "unspecified"))
    )
    (net (code "48") (name "unconnected-(P3-Pad12)") (class "Default")
      (node (ref "P3") (pin "12") (pinfunction "12_12") (pintype "unspecified"))
    )
    (net (code "49") (name "unconnected-(P3-Pad13)") (class "Default")
      (node (ref "P3") (pin "13") (pinfunction "13_13") (pintype "unspecified"))
    )
    (net (code "50") (name "unconnected-(P3-Pad14)") (class "Default")
      (node (ref "P3") (pin "14") (pinfunction "14_14") (pintype "unspecified"))
    )
    (net (code "51") (name "unconnected-(P3-Pad15)") (class "Default")
      (node (ref "P3") (pin "15") (pinfunction "15_15") (pintype "unspecified"))
    )
    (net (code "52") (name "unconnected-(P3-Pad16)") (class "Default")
      (node (ref "P3") (pin "16") (pinfunction "16_16") (pintype "unspecified"))
    )
    (net (code "53") (name "unconnected-(P3-Pad17)") (class "Default")
      (node (ref "P3") (pin "17") (pinfunction "17_17") (pintype "unspecified"))
    )
    (net (code "54") (name "unconnected-(P3-Pad18)") (class "Default")
      (node (ref "P3") (pin "18") (pinfunction "18_18") (pintype "unspecified"))
    )
    (net (code "55") (name "unconnected-(RV1-Pad4)") (class "Default")
      (node (ref "RV1") (pin "4") (pinfunction "4_4") (pintype "input"))
    )
    (net (code "56") (name "unconnected-(RV2-Pad4)") (class "Default")
      (node (ref "RV2") (pin "4") (pinfunction "4_4") (pintype "input"))
    )
    (net (code "57") (name "unconnected-(RV3-Pad4)") (class "Default")
      (node (ref "RV3") (pin "4") (pinfunction "4_4") (pintype "input"))
    )
    (net (code "58") (name "unconnected-(RV4-Pad4)") (class "Default")
      (node (ref "RV4") (pin "4") (pinfunction "4_4") (pintype "input"))
    )
    (net (code "59") (name "unconnected-(SW1-Pad3)") (class "Default")
      (node (ref "SW1") (pin "3") (pinfunction "3_3") (pintype "unspecified"))
    )
    (net (code "60") (name "unconnected-(SW1-Pad4)") (class "Default")
      (node (ref "SW1") (pin "4") (pinfunction "4_4") (pintype "unspecified"))
    )
    (net (code "61") (name "unconnected-(SW2-Pad1)") (class "Default")
      (node (ref "SW2") (pin "1") (pinfunction "1_1") (pintype "unspecified"))
    )
    (net (code "62") (name "unconnected-(SW2-Pad4)") (class "Default")
      (node (ref "SW2") (pin "4") (pinfunction "4_4") (pintype "unspecified"))
    )
    (net (code "63") (name "unconnected-(SW3-Pad1)") (class "Default")
      (node (ref "SW3") (pin "1") (pinfunction "1_1") (pintype "unspecified"))
    )
    (net (code "64") (name "unconnected-(SW3-Pad4)") (class "Default")
      (node (ref "SW3") (pin "4") (pinfunction "4_4") (pintype "unspecified"))
    )
    (net (code "65") (name "unconnected-(SW4-Pad1)") (class "Default")
      (node (ref "SW4") (pin "1") (pinfunction "1_1") (pintype "unspecified"))
    )
    (net (code "66") (name "unconnected-(SW4-Pad4)") (class "Default")
      (node (ref "SW4") (pin "4") (pinfunction "4_4") (pintype "unspecified"))
    )
    (net (code "67") (name "unconnected-(SW5-Pad1)") (class "Default")
      (node (ref "SW5") (pin "1") (pinfunction "1_1") (pintype "unspecified"))
    )
    (net (code "68") (name "unconnected-(SW5-Pad4)") (class "Default")
      (node (ref "SW5") (pin "4") (pinfunction "4_4") (pintype "unspecified"))
    )
    (net (code "69") (name "unconnected-(U1-OUT4#-Pad11)") (class "Default")
      (node (ref "U1") (pin "11") (pinfunction "OUT4#_11") (pintype "unspecified"))
    )
    (net (code "70") (name "unconnected-(U1-OUT5#-Pad12)") (class "Default")
      (node (ref "U1") (pin "12") (pinfunction "OUT5#_12") (pintype "unspecified"))
    )
    (net (code "71") (name "unconnected-(U1-OUT6#-Pad14)") (class "Default")
      (node (ref "U1") (pin "14") (pinfunction "OUT6#_14") (pintype "unspecified"))
    )
    (net (code "72") (name "unconnected-(U1-OUT7#-Pad15)") (class "Default")
      (node (ref "U1") (pin "15") (pinfunction "OUT7#_15") (pintype "unspecified"))
    )
    (net (code "73") (name "unconnected-(U3-ALERT{slash}RDY-Pad2)") (class "Default")
      (node (ref "U3") (pin "2") (pinfunction "ALERT/RDY_2") (pintype "unspecified"))
    )
  )
)
